# Z7_BANK_DDR3.net
KiCad netlist of a schematic drawn in Altium Designer
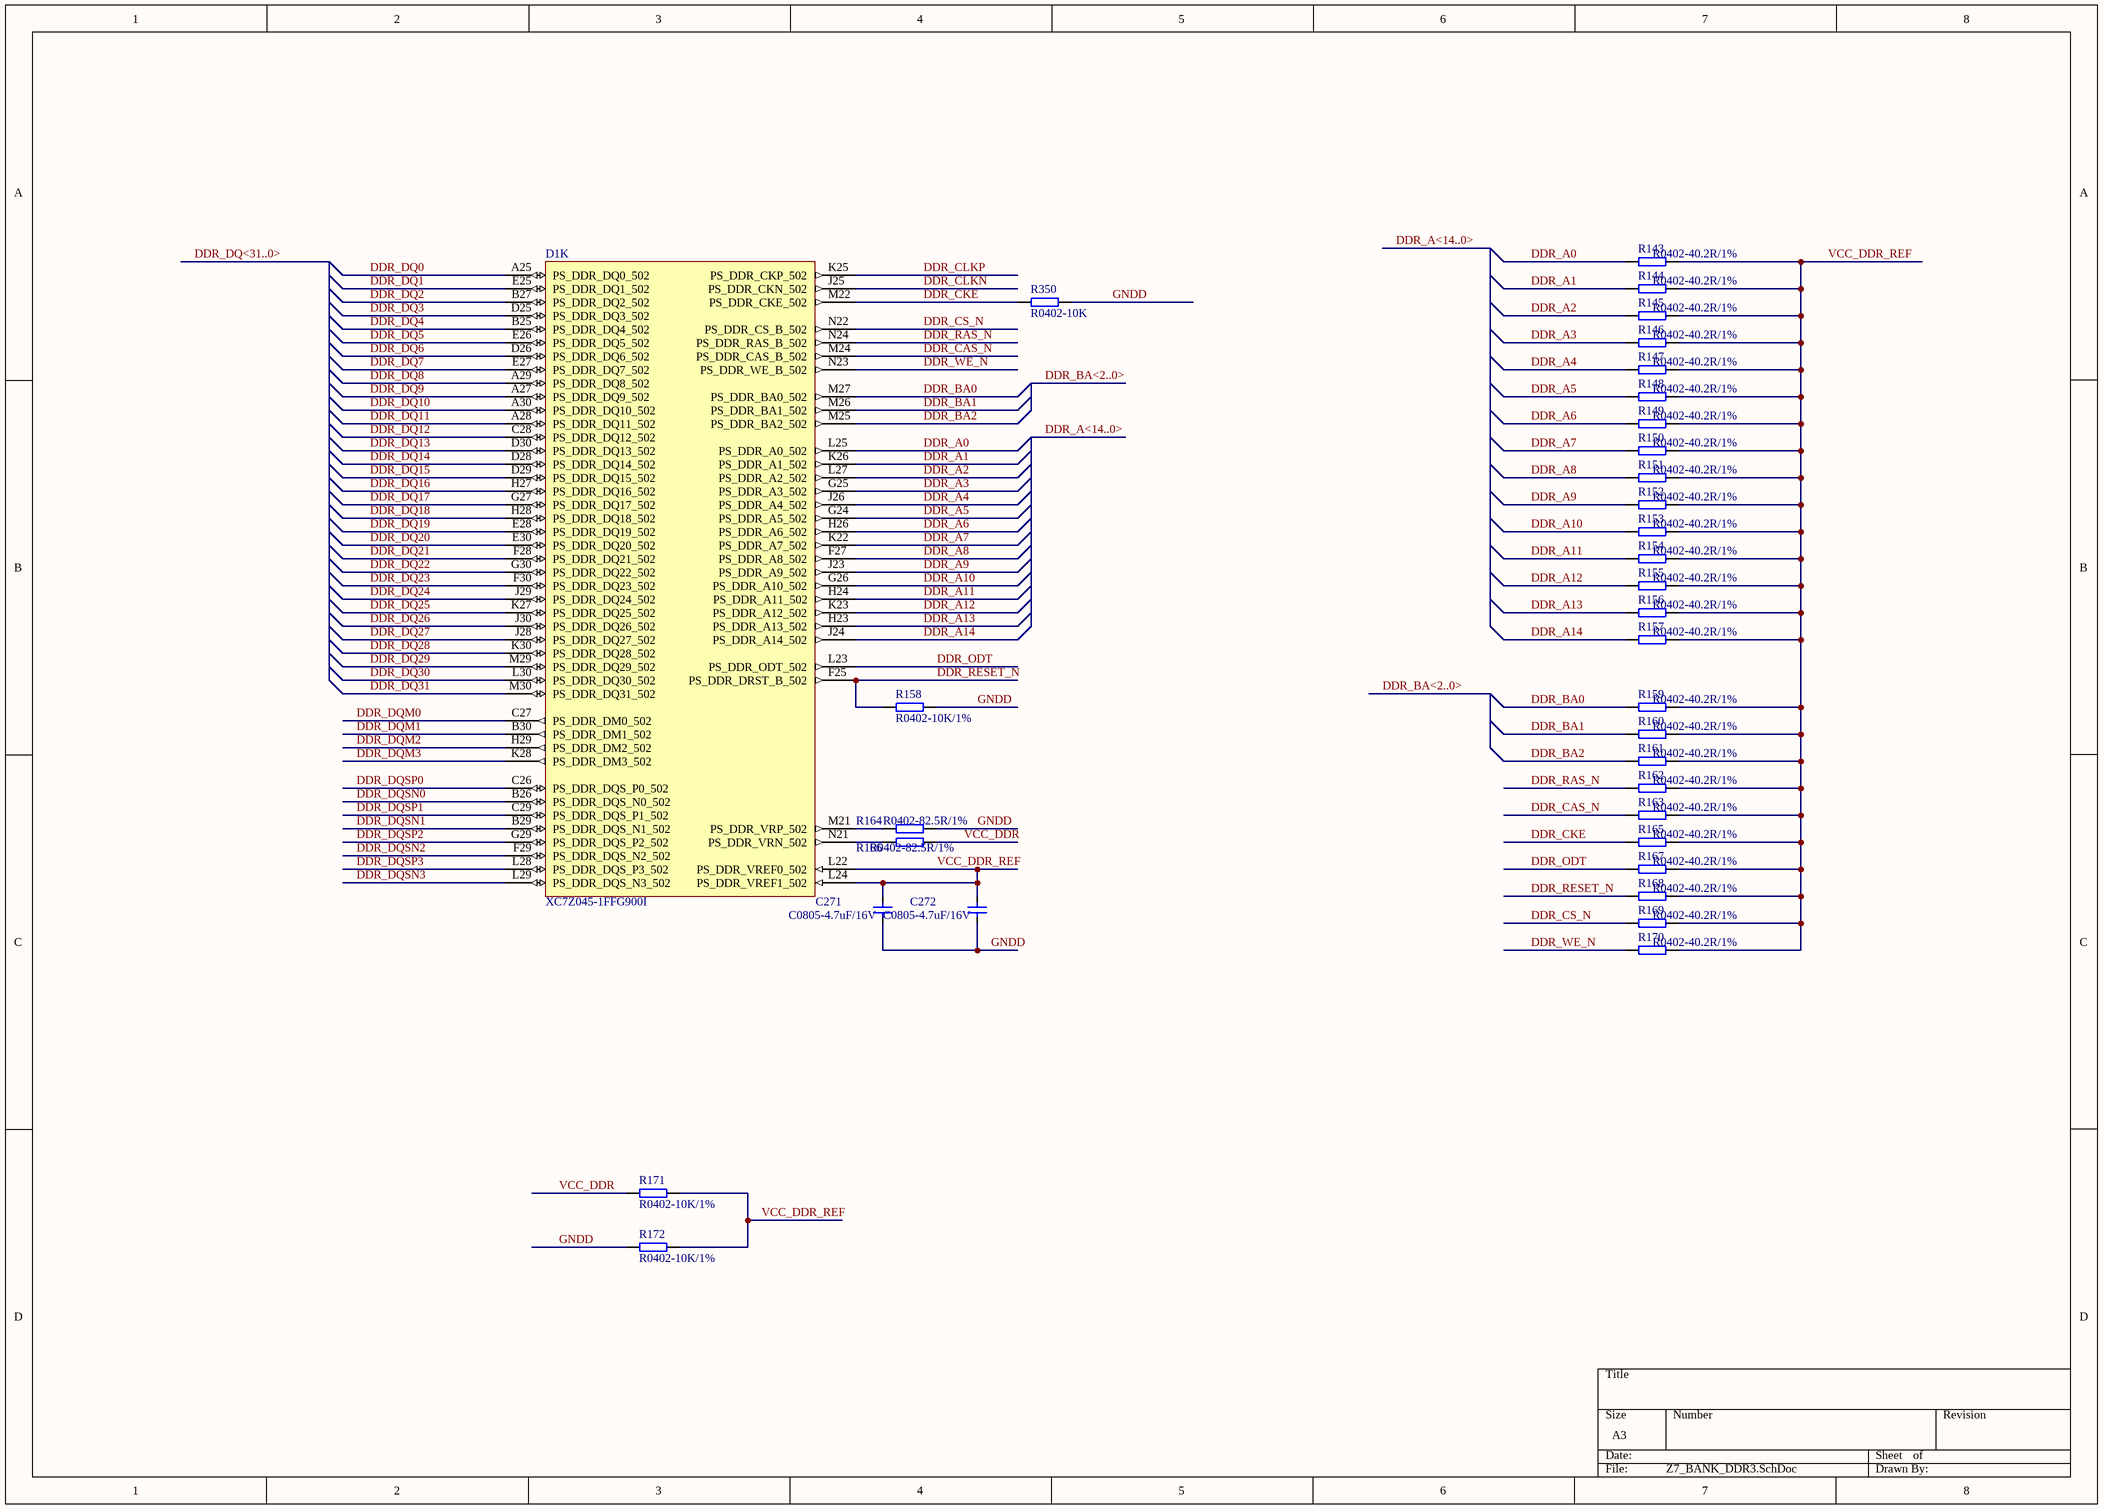
[diagram p0: Z7_BANK_DDR3.SchDoc]

(export (version "E")
  (design (tool "Eeschema 10.0.6"))
  (components
    (comp (ref "C271")
      (value "C0805-4.7uF/16V")
      (footprint "C0805")
      (description "X7R")
      (fields (field (name "SCHEMATIC_PART") "CAP") (field (name "MANUFACTURER") "SAMSUNG"))
      (libsource (lib "Database_Libs1") (part "CAP"))
    )
    (comp (ref "C272")
      (value "C0805-4.7uF/16V")
      (footprint "C0805")
      (description "X7R")
      (fields (field (name "SCHEMATIC_PART") "CAP") (field (name "MANUFACTURER") "SAMSUNG"))
      (libsource (lib "Database_Libs1") (part "CAP"))
    )
    (comp (ref "D1")
      (value "XC7Z045-1FFG900I")
      (footprint "FFG900")
      (fields (field (name "GENERIC PART NUMBER") "XC7Z045") (field (name "MANUFACTURER") "Xilinx"))
      (libsource (lib "Xilinx Zynq-7000") (part "XC7Z045-1FFG900I"))
    )
    (comp (ref "R143")
      (value "R0402-40.2R/1%")
      (footprint "R0402")
      (fields (field (name "SCHEMATIC_PART") "RES") (field (name "MANUFACTURER") "SAMSUNG"))
      (libsource (lib "Database_Libs1") (part "RES"))
    )
    (comp (ref "R144")
      (value "R0402-40.2R/1%")
      (footprint "R0402")
      (fields (field (name "SCHEMATIC_PART") "RES") (field (name "MANUFACTURER") "SAMSUNG"))
      (libsource (lib "Database_Libs1") (part "RES"))
    )
    (comp (ref "R145")
      (value "R0402-40.2R/1%")
      (footprint "R0402")
      (fields (field (name "SCHEMATIC_PART") "RES") (field (name "MANUFACTURER") "SAMSUNG"))
      (libsource (lib "Database_Libs1") (part "RES"))
    )
    (comp (ref "R146")
      (value "R0402-40.2R/1%")
      (footprint "R0402")
      (fields (field (name "SCHEMATIC_PART") "RES") (field (name "MANUFACTURER") "SAMSUNG"))
      (libsource (lib "Database_Libs1") (part "RES"))
    )
    (comp (ref "R147")
      (value "R0402-40.2R/1%")
      (footprint "R0402")
      (fields (field (name "SCHEMATIC_PART") "RES") (field (name "MANUFACTURER") "SAMSUNG"))
      (libsource (lib "Database_Libs1") (part "RES"))
    )
    (comp (ref "R148")
      (value "R0402-40.2R/1%")
      (footprint "R0402")
      (fields (field (name "SCHEMATIC_PART") "RES") (field (name "MANUFACTURER") "SAMSUNG"))
      (libsource (lib "Database_Libs1") (part "RES"))
    )
    (comp (ref "R149")
      (value "R0402-40.2R/1%")
      (footprint "R0402")
      (fields (field (name "SCHEMATIC_PART") "RES") (field (name "MANUFACTURER") "SAMSUNG"))
      (libsource (lib "Database_Libs1") (part "RES"))
    )
    (comp (ref "R150")
      (value "R0402-40.2R/1%")
      (footprint "R0402")
      (fields (field (name "SCHEMATIC_PART") "RES") (field (name "MANUFACTURER") "SAMSUNG"))
      (libsource (lib "Database_Libs1") (part "RES"))
    )
    (comp (ref "R151")
      (value "R0402-40.2R/1%")
      (footprint "R0402")
      (fields (field (name "SCHEMATIC_PART") "RES") (field (name "MANUFACTURER") "SAMSUNG"))
      (libsource (lib "Database_Libs1") (part "RES"))
    )
    (comp (ref "R152")
      (value "R0402-40.2R/1%")
      (footprint "R0402")
      (fields (field (name "SCHEMATIC_PART") "RES") (field (name "MANUFACTURER") "SAMSUNG"))
      (libsource (lib "Database_Libs1") (part "RES"))
    )
    (comp (ref "R153")
      (value "R0402-40.2R/1%")
      (footprint "R0402")
      (fields (field (name "SCHEMATIC_PART") "RES") (field (name "MANUFACTURER") "SAMSUNG"))
      (libsource (lib "Database_Libs1") (part "RES"))
    )
    (comp (ref "R154")
      (value "R0402-40.2R/1%")
      (footprint "R0402")
      (fields (field (name "SCHEMATIC_PART") "RES") (field (name "MANUFACTURER") "SAMSUNG"))
      (libsource (lib "Database_Libs1") (part "RES"))
    )
    (comp (ref "R155")
      (value "R0402-40.2R/1%")
      (footprint "R0402")
      (fields (field (name "SCHEMATIC_PART") "RES") (field (name "MANUFACTURER") "SAMSUNG"))
      (libsource (lib "Database_Libs1") (part "RES"))
    )
    (comp (ref "R156")
      (value "R0402-40.2R/1%")
      (footprint "R0402")
      (fields (field (name "SCHEMATIC_PART") "RES") (field (name "MANUFACTURER") "SAMSUNG"))
      (libsource (lib "Database_Libs1") (part "RES"))
    )
    (comp (ref "R157")
      (value "R0402-40.2R/1%")
      (footprint "R0402")
      (fields (field (name "SCHEMATIC_PART") "RES") (field (name "MANUFACTURER") "SAMSUNG"))
      (libsource (lib "Database_Libs1") (part "RES"))
    )
    (comp (ref "R158")
      (value "R0402-10K/1%")
      (footprint "R0402")
      (fields (field (name "SCHEMATIC_PART") "RES") (field (name "MANUFACTURER") "SAMSUNG"))
      (libsource (lib "Database_Libs1") (part "RES"))
    )
    (comp (ref "R159")
      (value "R0402-40.2R/1%")
      (footprint "R0402")
      (fields (field (name "SCHEMATIC_PART") "RES") (field (name "MANUFACTURER") "SAMSUNG"))
      (libsource (lib "Database_Libs1") (part "RES"))
    )
    (comp (ref "R160")
      (value "R0402-40.2R/1%")
      (footprint "R0402")
      (fields (field (name "SCHEMATIC_PART") "RES") (field (name "MANUFACTURER") "SAMSUNG"))
      (libsource (lib "Database_Libs1") (part "RES"))
    )
    (comp (ref "R161")
      (value "R0402-40.2R/1%")
      (footprint "R0402")
      (fields (field (name "SCHEMATIC_PART") "RES") (field (name "MANUFACTURER") "SAMSUNG"))
      (libsource (lib "Database_Libs1") (part "RES"))
    )
    (comp (ref "R162")
      (value "R0402-40.2R/1%")
      (footprint "R0402")
      (fields (field (name "SCHEMATIC_PART") "RES") (field (name "MANUFACTURER") "SAMSUNG"))
      (libsource (lib "Database_Libs1") (part "RES"))
    )
    (comp (ref "R163")
      (value "R0402-40.2R/1%")
      (footprint "R0402")
      (fields (field (name "SCHEMATIC_PART") "RES") (field (name "MANUFACTURER") "SAMSUNG"))
      (libsource (lib "Database_Libs1") (part "RES"))
    )
    (comp (ref "R164")
      (value "R0402-82.5R/1%")
      (footprint "R0402")
      (fields (field (name "SCHEMATIC_PART") "RES") (field (name "MANUFACTURER") "SAMSUNG"))
      (libsource (lib "Database_Libs1") (part "RES"))
    )
    (comp (ref "R165")
      (value "R0402-40.2R/1%")
      (footprint "R0402")
      (fields (field (name "SCHEMATIC_PART") "RES") (field (name "MANUFACTURER") "SAMSUNG"))
      (libsource (lib "Database_Libs1") (part "RES"))
    )
    (comp (ref "R166")
      (value "R0402-82.5R/1%")
      (footprint "R0402")
      (fields (field (name "SCHEMATIC_PART") "RES") (field (name "MANUFACTURER") "SAMSUNG"))
      (libsource (lib "Database_Libs1") (part "RES"))
    )
    (comp (ref "R167")
      (value "R0402-40.2R/1%")
      (footprint "R0402")
      (fields (field (name "SCHEMATIC_PART") "RES") (field (name "MANUFACTURER") "SAMSUNG"))
      (libsource (lib "Database_Libs1") (part "RES"))
    )
    (comp (ref "R168")
      (value "R0402-40.2R/1%")
      (footprint "R0402")
      (fields (field (name "SCHEMATIC_PART") "RES") (field (name "MANUFACTURER") "SAMSUNG"))
      (libsource (lib "Database_Libs1") (part "RES"))
    )
    (comp (ref "R169")
      (value "R0402-40.2R/1%")
      (footprint "R0402")
      (fields (field (name "SCHEMATIC_PART") "RES") (field (name "MANUFACTURER") "SAMSUNG"))
      (libsource (lib "Database_Libs1") (part "RES"))
    )
    (comp (ref "R170")
      (value "R0402-40.2R/1%")
      (footprint "R0402")
      (fields (field (name "SCHEMATIC_PART") "RES") (field (name "MANUFACTURER") "SAMSUNG"))
      (libsource (lib "Database_Libs1") (part "RES"))
    )
    (comp (ref "R171")
      (value "R0402-10K/1%")
      (footprint "R0402")
      (fields (field (name "SCHEMATIC_PART") "RES") (field (name "MANUFACTURER") "SAMSUNG"))
      (libsource (lib "Database_Libs1") (part "RES"))
    )
    (comp (ref "R172")
      (value "R0402-10K/1%")
      (footprint "R0402")
      (fields (field (name "SCHEMATIC_PART") "RES") (field (name "MANUFACTURER") "SAMSUNG"))
      (libsource (lib "Database_Libs1") (part "RES"))
    )
    (comp (ref "R350")
      (value "R0402-10K")
      (footprint "R0402")
      (fields (field (name "SCHEMATIC_PART") "RES") (field (name "MANUFACTURER") "SAMSUNG"))
      (libsource (lib "Database_Libs1") (part "RES"))
    )
  )
  (nets
    (net (code "4") (name "/DDR_A0") (class "Default")
      (node (ref "D1") (pin "L25") (pinfunction "PS_DDR_A0_502_L25") (pintype "output"))
      (node (ref "R143") (pin "1") (pintype "passive"))
    )
    (net (code "5") (name "/DDR_A1") (class "Default")
      (node (ref "D1") (pin "K26") (pinfunction "PS_DDR_A1_502_K26") (pintype "output"))
      (node (ref "R144") (pin "1") (pintype "passive"))
    )
    (net (code "6") (name "/DDR_A2") (class "Default")
      (node (ref "D1") (pin "L27") (pinfunction "PS_DDR_A2_502_L27") (pintype "output"))
      (node (ref "R145") (pin "1") (pintype "passive"))
    )
    (net (code "7") (name "/DDR_A3") (class "Default")
      (node (ref "D1") (pin "G25") (pinfunction "PS_DDR_A3_502_G25") (pintype "output"))
      (node (ref "R146") (pin "1") (pintype "passive"))
    )
    (net (code "8") (name "/DDR_A4") (class "Default")
      (node (ref "D1") (pin "J26") (pinfunction "PS_DDR_A4_502_J26") (pintype "output"))
      (node (ref "R147") (pin "1") (pintype "passive"))
    )
    (net (code "9") (name "/DDR_A5") (class "Default")
      (node (ref "D1") (pin "G24") (pinfunction "PS_DDR_A5_502_G24") (pintype "output"))
      (node (ref "R148") (pin "1") (pintype "passive"))
    )
    (net (code "10") (name "/DDR_A6") (class "Default")
      (node (ref "D1") (pin "H26") (pinfunction "PS_DDR_A6_502_H26") (pintype "output"))
      (node (ref "R149") (pin "1") (pintype "passive"))
    )
    (net (code "11") (name "/DDR_A7") (class "Default")
      (node (ref "D1") (pin "K22") (pinfunction "PS_DDR_A7_502_K22") (pintype "output"))
      (node (ref "R150") (pin "1") (pintype "passive"))
    )
    (net (code "12") (name "/DDR_A8") (class "Default")
      (node (ref "D1") (pin "F27") (pinfunction "PS_DDR_A8_502_F27") (pintype "output"))
      (node (ref "R151") (pin "1") (pintype "passive"))
    )
    (net (code "13") (name "/DDR_A9") (class "Default")
      (node (ref "D1") (pin "J23") (pinfunction "PS_DDR_A9_502_J23") (pintype "output"))
      (node (ref "R152") (pin "1") (pintype "passive"))
    )
    (net (code "14") (name "/DDR_A10") (class "Default")
      (node (ref "D1") (pin "G26") (pinfunction "PS_DDR_A10_502_G26") (pintype "output"))
      (node (ref "R153") (pin "1") (pintype "passive"))
    )
    (net (code "15") (name "/DDR_A11") (class "Default")
      (node (ref "D1") (pin "H24") (pinfunction "PS_DDR_A11_502_H24") (pintype "output"))
      (node (ref "R154") (pin "1") (pintype "passive"))
    )
    (net (code "16") (name "/DDR_A12") (class "Default")
      (node (ref "D1") (pin "K23") (pinfunction "PS_DDR_A12_502_K23") (pintype "output"))
      (node (ref "R155") (pin "1") (pintype "passive"))
    )
    (net (code "17") (name "/DDR_A13") (class "Default")
      (node (ref "D1") (pin "H23") (pinfunction "PS_DDR_A13_502_H23") (pintype "output"))
      (node (ref "R156") (pin "1") (pintype "passive"))
    )
    (net (code "18") (name "/DDR_A14") (class "Default")
      (node (ref "D1") (pin "J24") (pinfunction "PS_DDR_A14_502_J24") (pintype "output"))
      (node (ref "R157") (pin "1") (pintype "passive"))
    )
    (net (code "19") (name "/DDR_BA0") (class "Default")
      (node (ref "D1") (pin "M27") (pinfunction "PS_DDR_BA0_502_M27") (pintype "output"))
      (node (ref "R159") (pin "1") (pintype "passive"))
    )
    (net (code "20") (name "/DDR_BA1") (class "Default")
      (node (ref "D1") (pin "M26") (pinfunction "PS_DDR_BA1_502_M26") (pintype "output"))
      (node (ref "R160") (pin "1") (pintype "passive"))
    )
    (net (code "21") (name "/DDR_BA2") (class "Default")
      (node (ref "D1") (pin "M25") (pinfunction "PS_DDR_BA2_502_M25") (pintype "output"))
      (node (ref "R161") (pin "1") (pintype "passive"))
    )
    (net (code "22") (name "/DDR_CAS_N") (class "Default")
      (node (ref "D1") (pin "M24") (pinfunction "PS_DDR_CAS_B_502_M24") (pintype "output"))
      (node (ref "R163") (pin "1") (pintype "passive"))
    )
    (net (code "23") (name "/DDR_CKE") (class "Default")
      (node (ref "D1") (pin "M22") (pinfunction "PS_DDR_CKE_502_M22") (pintype "output"))
      (node (ref "R165") (pin "1") (pintype "passive"))
      (node (ref "R350") (pin "2") (pintype "passive"))
    )
    (net (code "24") (name "/DDR_CLKN") (class "Default")
      (node (ref "D1") (pin "J25") (pinfunction "PS_DDR_CKN_502_J25") (pintype "output"))
    )
    (net (code "25") (name "/DDR_CLKP") (class "Default")
      (node (ref "D1") (pin "K25") (pinfunction "PS_DDR_CKP_502_K25") (pintype "output"))
    )
    (net (code "26") (name "/DDR_CS_N") (class "Default")
      (node (ref "D1") (pin "N22") (pinfunction "PS_DDR_CS_B_502_N22") (pintype "output"))
      (node (ref "R169") (pin "1") (pintype "passive"))
    )
    (net (code "27") (name "/DDR_DQ0") (class "Default")
      (node (ref "D1") (pin "A25") (pinfunction "PS_DDR_DQ0_502_A25") (pintype "bidirectional"))
    )
    (net (code "28") (name "/DDR_DQ1") (class "Default")
      (node (ref "D1") (pin "E25") (pinfunction "PS_DDR_DQ1_502_E25") (pintype "bidirectional"))
    )
    (net (code "29") (name "/DDR_DQ2") (class "Default")
      (node (ref "D1") (pin "B27") (pinfunction "PS_DDR_DQ2_502_B27") (pintype "bidirectional"))
    )
    (net (code "30") (name "/DDR_DQ3") (class "Default")
      (node (ref "D1") (pin "D25") (pinfunction "PS_DDR_DQ3_502_D25") (pintype "bidirectional"))
    )
    (net (code "31") (name "/DDR_DQ4") (class "Default")
      (node (ref "D1") (pin "B25") (pinfunction "PS_DDR_DQ4_502_B25") (pintype "bidirectional"))
    )
    (net (code "32") (name "/DDR_DQ5") (class "Default")
      (node (ref "D1") (pin "E26") (pinfunction "PS_DDR_DQ5_502_E26") (pintype "bidirectional"))
    )
    (net (code "33") (name "/DDR_DQ6") (class "Default")
      (node (ref "D1") (pin "D26") (pinfunction "PS_DDR_DQ6_502_D26") (pintype "bidirectional"))
    )
    (net (code "34") (name "/DDR_DQ7") (class "Default")
      (node (ref "D1") (pin "E27") (pinfunction "PS_DDR_DQ7_502_E27") (pintype "bidirectional"))
    )
    (net (code "35") (name "/DDR_DQ8") (class "Default")
      (node (ref "D1") (pin "A29") (pinfunction "PS_DDR_DQ8_502_A29") (pintype "bidirectional"))
    )
    (net (code "36") (name "/DDR_DQ9") (class "Default")
      (node (ref "D1") (pin "A27") (pinfunction "PS_DDR_DQ9_502_A27") (pintype "bidirectional"))
    )
    (net (code "37") (name "/DDR_DQ10") (class "Default")
      (node (ref "D1") (pin "A30") (pinfunction "PS_DDR_DQ10_502_A30") (pintype "bidirectional"))
    )
    (net (code "38") (name "/DDR_DQ11") (class "Default")
      (node (ref "D1") (pin "A28") (pinfunction "PS_DDR_DQ11_502_A28") (pintype "bidirectional"))
    )
    (net (code "39") (name "/DDR_DQ12") (class "Default")
      (node (ref "D1") (pin "C28") (pinfunction "PS_DDR_DQ12_502_C28") (pintype "bidirectional"))
    )
    (net (code "40") (name "/DDR_DQ13") (class "Default")
      (node (ref "D1") (pin "D30") (pinfunction "PS_DDR_DQ13_502_D30") (pintype "bidirectional"))
    )
    (net (code "41") (name "/DDR_DQ14") (class "Default")
      (node (ref "D1") (pin "D28") (pinfunction "PS_DDR_DQ14_502_D28") (pintype "bidirectional"))
    )
    (net (code "42") (name "/DDR_DQ15") (class "Default")
      (node (ref "D1") (pin "D29") (pinfunction "PS_DDR_DQ15_502_D29") (pintype "bidirectional"))
    )
    (net (code "43") (name "/DDR_DQ16") (class "Default")
      (node (ref "D1") (pin "H27") (pinfunction "PS_DDR_DQ16_502_H27") (pintype "bidirectional"))
    )
    (net (code "44") (name "/DDR_DQ17") (class "Default")
      (node (ref "D1") (pin "G27") (pinfunction "PS_DDR_DQ17_502_G27") (pintype "bidirectional"))
    )
    (net (code "45") (name "/DDR_DQ18") (class "Default")
      (node (ref "D1") (pin "H28") (pinfunction "PS_DDR_DQ18_502_H28") (pintype "bidirectional"))
    )
    (net (code "46") (name "/DDR_DQ19") (class "Default")
      (node (ref "D1") (pin "E28") (pinfunction "PS_DDR_DQ19_502_E28") (pintype "bidirectional"))
    )
    (net (code "47") (name "/DDR_DQ20") (class "Default")
      (node (ref "D1") (pin "E30") (pinfunction "PS_DDR_DQ20_502_E30") (pintype "bidirectional"))
    )
    (net (code "48") (name "/DDR_DQ21") (class "Default")
      (node (ref "D1") (pin "F28") (pinfunction "PS_DDR_DQ21_502_F28") (pintype "bidirectional"))
    )
    (net (code "49") (name "/DDR_DQ22") (class "Default")
      (node (ref "D1") (pin "G30") (pinfunction "PS_DDR_DQ22_502_G30") (pintype "bidirectional"))
    )
    (net (code "50") (name "/DDR_DQ23") (class "Default")
      (node (ref "D1") (pin "F30") (pinfunction "PS_DDR_DQ23_502_F30") (pintype "bidirectional"))
    )
    (net (code "51") (name "/DDR_DQ24") (class "Default")
      (node (ref "D1") (pin "J29") (pinfunction "PS_DDR_DQ24_502_J29") (pintype "bidirectional"))
    )
    (net (code "52") (name "/DDR_DQ25") (class "Default")
      (node (ref "D1") (pin "K27") (pinfunction "PS_DDR_DQ25_502_K27") (pintype "bidirectional"))
    )
    (net (code "53") (name "/DDR_DQ26") (class "Default")
      (node (ref "D1") (pin "J30") (pinfunction "PS_DDR_DQ26_502_J30") (pintype "bidirectional"))
    )
    (net (code "54") (name "/DDR_DQ27") (class "Default")
      (node (ref "D1") (pin "J28") (pinfunction "PS_DDR_DQ27_502_J28") (pintype "bidirectional"))
    )
    (net (code "55") (name "/DDR_DQ28") (class "Default")
      (node (ref "D1") (pin "K30") (pinfunction "PS_DDR_DQ28_502_K30") (pintype "bidirectional"))
    )
    (net (code "56") (name "/DDR_DQ29") (class "Default")
      (node (ref "D1") (pin "M29") (pinfunction "PS_DDR_DQ29_502_M29") (pintype "bidirectional"))
    )
    (net (code "57") (name "/DDR_DQ30") (class "Default")
      (node (ref "D1") (pin "L30") (pinfunction "PS_DDR_DQ30_502_L30") (pintype "bidirectional"))
    )
    (net (code "58") (name "/DDR_DQ31") (class "Default")
      (node (ref "D1") (pin "M30") (pinfunction "PS_DDR_DQ31_502_M30") (pintype "bidirectional"))
    )
    (net (code "59") (name "/DDR_DQM0") (class "Default")
      (node (ref "D1") (pin "C27") (pinfunction "PS_DDR_DM0_502_C27") (pintype "output"))
    )
    (net (code "60") (name "/DDR_DQM1") (class "Default")
      (node (ref "D1") (pin "B30") (pinfunction "PS_DDR_DM1_502_B30") (pintype "output"))
    )
    (net (code "61") (name "/DDR_DQM2") (class "Default")
      (node (ref "D1") (pin "H29") (pinfunction "PS_DDR_DM2_502_H29") (pintype "output"))
    )
    (net (code "62") (name "/DDR_DQM3") (class "Default")
      (node (ref "D1") (pin "K28") (pinfunction "PS_DDR_DM3_502_K28") (pintype "output"))
    )
    (net (code "63") (name "/DDR_DQSN0") (class "Default")
      (node (ref "D1") (pin "B26") (pinfunction "PS_DDR_DQS_N0_502_B26") (pintype "bidirectional"))
    )
    (net (code "64") (name "/DDR_DQSN1") (class "Default")
      (node (ref "D1") (pin "B29") (pinfunction "PS_DDR_DQS_N1_502_B29") (pintype "bidirectional"))
    )
    (net (code "65") (name "/DDR_DQSN2") (class "Default")
      (node (ref "D1") (pin "F29") (pinfunction "PS_DDR_DQS_N2_502_F29") (pintype "bidirectional"))
    )
    (net (code "66") (name "/DDR_DQSN3") (class "Default")
      (node (ref "D1") (pin "L29") (pinfunction "PS_DDR_DQS_N3_502_L29") (pintype "bidirectional"))
    )
    (net (code "67") (name "/DDR_DQSP0") (class "Default")
      (node (ref "D1") (pin "C26") (pinfunction "PS_DDR_DQS_P0_502_C26") (pintype "bidirectional"))
    )
    (net (code "68") (name "/DDR_DQSP1") (class "Default")
      (node (ref "D1") (pin "C29") (pinfunction "PS_DDR_DQS_P1_502_C29") (pintype "bidirectional"))
    )
    (net (code "69") (name "/DDR_DQSP2") (class "Default")
      (node (ref "D1") (pin "G29") (pinfunction "PS_DDR_DQS_P2_502_G29") (pintype "bidirectional"))
    )
    (net (code "70") (name "/DDR_DQSP3") (class "Default")
      (node (ref "D1") (pin "L28") (pinfunction "PS_DDR_DQS_P3_502_L28") (pintype "bidirectional"))
    )
    (net (code "71") (name "/DDR_ODT") (class "Default")
      (node (ref "D1") (pin "L23") (pinfunction "PS_DDR_ODT_502_L23") (pintype "output"))
      (node (ref "R167") (pin "1") (pintype "passive"))
    )
    (net (code "72") (name "/DDR_RAS_N") (class "Default")
      (node (ref "D1") (pin "N24") (pinfunction "PS_DDR_RAS_B_502_N24") (pintype "output"))
      (node (ref "R162") (pin "1") (pintype "passive"))
    )
    (net (code "73") (name "/DDR_RESET_N") (class "Default")
      (node (ref "D1") (pin "F25") (pinfunction "PS_DDR_DRST_B_502_F25") (pintype "output"))
      (node (ref "R158") (pin "2") (pintype "passive"))
      (node (ref "R168") (pin "1") (pintype "passive"))
    )
    (net (code "74") (name "/DDR_WE_N") (class "Default")
      (node (ref "D1") (pin "N23") (pinfunction "PS_DDR_WE_B_502_N23") (pintype "output"))
      (node (ref "R170") (pin "1") (pintype "passive"))
    )
    (net (code "75") (name "/GNDD") (class "Default")
      (node (ref "C271") (pin "2") (pinfunction "2_2") (pintype "passive"))
      (node (ref "C272") (pin "2") (pinfunction "2_2") (pintype "passive"))
      (node (ref "R158") (pin "1") (pintype "passive"))
      (node (ref "R164") (pin "1") (pintype "passive"))
      (node (ref "R172") (pin "2") (pintype "passive"))
      (node (ref "R350") (pin "1") (pintype "passive"))
    )
    (net (code "76") (name "/VCC_DDR") (class "Default")
      (node (ref "R166") (pin "1") (pintype "passive"))
      (node (ref "R171") (pin "2") (pintype "passive"))
    )
    (net (code "77") (name "/VCC_DDR_REF") (class "Default")
      (node (ref "C271") (pin "1") (pinfunction "1_1") (pintype "passive"))
      (node (ref "C272") (pin "1") (pinfunction "1_1") (pintype "passive"))
      (node (ref "D1") (pin "L22") (pinfunction "PS_DDR_VREF0_502_L22") (pintype "input"))
      (node (ref "D1") (pin "L24") (pinfunction "PS_DDR_VREF1_502_L24") (pintype "input"))
      (node (ref "R143") (pin "2") (pintype "passive"))
      (node (ref "R144") (pin "2") (pintype "passive"))
      (node (ref "R145") (pin "2") (pintype "passive"))
      (node (ref "R146") (pin "2") (pintype "passive"))
      (node (ref "R147") (pin "2") (pintype "passive"))
      (node (ref "R148") (pin "2") (pintype "passive"))
      (node (ref "R149") (pin "2") (pintype "passive"))
      (node (ref "R150") (pin "2") (pintype "passive"))
      (node (ref "R151") (pin "2") (pintype "passive"))
      (node (ref "R152") (pin "2") (pintype "passive"))
      (node (ref "R153") (pin "2") (pintype "passive"))
      (node (ref "R154") (pin "2") (pintype "passive"))
      (node (ref "R155") (pin "2") (pintype "passive"))
      (node (ref "R156") (pin "2") (pintype "passive"))
      (node (ref "R157") (pin "2") (pintype "passive"))
      (node (ref "R159") (pin "2") (pintype "passive"))
      (node (ref "R160") (pin "2") (pintype "passive"))
      (node (ref "R161") (pin "2") (pintype "passive"))
      (node (ref "R162") (pin "2") (pintype "passive"))
      (node (ref "R163") (pin "2") (pintype "passive"))
      (node (ref "R165") (pin "2") (pintype "passive"))
      (node (ref "R167") (pin "2") (pintype "passive"))
      (node (ref "R168") (pin "2") (pintype "passive"))
      (node (ref "R169") (pin "2") (pintype "passive"))
      (node (ref "R170") (pin "2") (pintype "passive"))
      (node (ref "R171") (pin "1") (pintype "passive"))
      (node (ref "R172") (pin "1") (pintype "passive"))
    )
    (net (code "81") (name "Net-(D1K-PS_DDR_VRN_502)") (class "Default")
      (node (ref "D1") (pin "N21") (pinfunction "PS_DDR_VRN_502_N21") (pintype "output"))
      (node (ref "R166") (pin "2") (pintype "passive"))
    )
    (net (code "82") (name "Net-(D1K-PS_DDR_VRP_502)") (class "Default")
      (node (ref "D1") (pin "M21") (pinfunction "PS_DDR_VRP_502_M21") (pintype "output"))
      (node (ref "R164") (pin "2") (pintype "passive"))
    )
  )
)
